# maindoline.net
KiCad netlist of a schematic drawn in Altium Designer
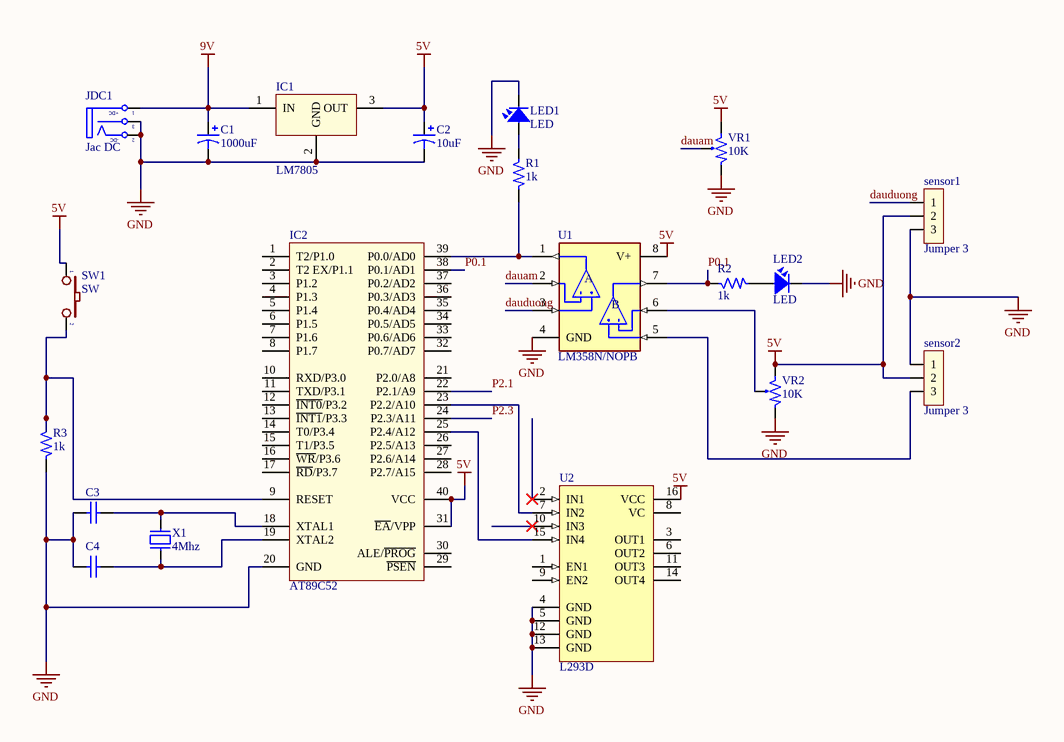
[diagram p0: maindoline.SchDoc]

(export (version "E")
  (design (tool "Eeschema 10.0.6"))
  (components
    (comp (ref "C1")
      (value "1000uF")
      (footprint "C5mm")
      (description "Polarized Capacitor (Axial)")
      (fields (field (name "PUBLISHER") "Altium Limited"))
      (libsource (lib "My Library") (part "Cap Pol 5mm"))
    )
    (comp (ref "C2")
      (value "10uF")
      (footprint "C5mm")
      (description "Polarized Capacitor (Axial)")
      (fields (field (name "PUBLISHER") "Altium Limited"))
      (libsource (lib "My Library") (part "Cap Pol 5mm"))
    )
    (comp (ref "C3")
      (value "22pF")
      (footprint "C0805")
      (description "Capacitor")
      (fields (field (name "PUBLISHER") "Altium Limited"))
      (libsource (lib "My Library") (part "CapSMD"))
    )
    (comp (ref "C4")
      (value "22pF")
      (footprint "C0805")
      (description "Capacitor")
      (fields (field (name "PUBLISHER") "Altium Limited"))
      (libsource (lib "My Library") (part "CapSMD"))
    )
    (comp (ref "IC1")
      (value "LM7805")
      (footprint "QTO-220")
      (description "On ap +, from + 5 to + 24VDC")
      (libsource (lib "My Library") (part "LM78xx"))
    )
    (comp (ref "IC2")
      (value "AT89C52")
      (footprint "DIP40/W0.6")
      (description "Atmel AT89C52, 8k Byte Flash Memory , 40 Pin")
      (libsource (lib "My Library") (part "AT89C52"))
    )
    (comp (ref "JDC1")
      (value "Jac DC")
      (footprint "DC-IN")
      (description "Jac DC input")
      (libsource (lib "My Library") (part "DCIN"))
    )
    (comp (ref "LED1")
      (value "LED")
      (footprint "LED-3")
      (description "LED Single colour Green and Red")
      (libsource (lib "My Library") (part "LED"))
    )
    (comp (ref "LED2")
      (value "LED")
      (footprint "LED-3")
      (description "LED Single colour Green and Red")
      (libsource (lib "My Library") (part "LED"))
    )
    (comp (ref "R1")
      (value "1k")
      (footprint "RES-SMD-0805")
      (description "Resistor 1/4W")
      (libsource (lib "My Library") (part "R"))
    )
    (comp (ref "R2")
      (value "1k")
      (footprint "RES-SMD-0805")
      (description "Resistor 1/4W")
      (libsource (lib "My Library") (part "R"))
    )
    (comp (ref "R3")
      (value "1k")
      (footprint "RES-SMD-0805")
      (description "Resistor 1/4W")
      (libsource (lib "My Library") (part "R"))
    )
    (comp (ref "sensor1") (value "Jumper 3") (footprint "JP3") (libsource (lib "My Library") (part "JP3")))
    (comp (ref "sensor2") (value "Jumper 3") (footprint "JP3") (libsource (lib "My Library") (part "JP3")))
    (comp (ref "SW1")
      (value "SW")
      (footprint "SW2")
      (description "Switch button 2 pin")
      (libsource (lib "My Library") (part "SW2"))
    )
    (comp (ref "U1")
      (value "LM358N/NOPB")
      (footprint "DIP794W45P254L959H508Q8")
      (libsource (lib "LM358N_NOPB") (part "LM358N/NOPB"))
    )
    (comp (ref "U2")
      (value "L293D")
      (footprint "DIP880W50P254L2000H510Q16")
      (description "Push-Pull Four Channel Driver With Diode")
      (fields (field (name "PUBLISHER") "Altium Limited"))
      (libsource (lib "My Library") (part "L293D"))
    )
    (comp (ref "VR1")
      (value "10K")
      (footprint "VR")
      (description "Var Resistor")
      (libsource (lib "My Library") (part "VR1"))
    )
    (comp (ref "VR2")
      (value "10K")
      (footprint "VR")
      (description "Var Resistor")
      (libsource (lib "My Library") (part "VR1"))
    )
    (comp (ref "X1")
      (value "4Mhz")
      (footprint "XT2")
      (description "Crystal For all Crystal 2pin.")
      (libsource (lib "My Library") (part "XT2"))
    )
  )
  (nets
    (net (code "1") (name "/P0.1") (class "Default")
      (node (ref "IC2") (pin "38") (pinfunction "P0.1/AD1_38") (pintype "passive"))
      (node (ref "R2") (pin "1") (pinfunction "1_1") (pintype "passive"))
      (node (ref "U1") (pin "7") (pinfunction "OUTB_7") (pintype "output"))
    )
    (net (code "2") (name "/P2.1") (class "Default")
      (node (ref "IC2") (pin "22") (pinfunction "P2.1/A9_22") (pintype "passive"))
    )
    (net (code "3") (name "/P2.3") (class "Default")
      (node (ref "IC2") (pin "24") (pinfunction "P2.3/A11_24") (pintype "passive"))
    )
    (net (code "4") (name "/dauam") (class "Default")
      (node (ref "U1") (pin "2") (pinfunction "-INA_2") (pintype "input"))
      (node (ref "VR1") (pin "2") (pinfunction "2_2") (pintype "passive"))
    )
    (net (code "5") (name "/dauduong") (class "Default")
      (node (ref "U1") (pin "3") (pinfunction "+INA_3") (pintype "input"))
      (node (ref "sensor1") (pin "1") (pinfunction "1_1") (pintype "passive"))
    )
    (net (code "6") (name "5V") (class "Default")
      (node (ref "C2") (pin "1") (pinfunction "1_1") (pintype "passive"))
      (node (ref "IC1") (pin "3") (pinfunction "OUT_3") (pintype "passive"))
      (node (ref "IC2") (pin "31") (pinfunction "~{EA}/VPP_31") (pintype "passive"))
      (node (ref "IC2") (pin "40") (pinfunction "VCC_40") (pintype "power_in"))
      (node (ref "SW1") (pin "1") (pinfunction "1_1") (pintype "passive"))
      (node (ref "U1") (pin "8") (pinfunction "V+_8") (pintype "power_in"))
      (node (ref "U2") (pin "16") (pinfunction "VCC_16") (pintype "power_in"))
      (node (ref "VR1") (pin "3") (pinfunction "3_3") (pintype "passive"))
      (node (ref "VR2") (pin "3") (pinfunction "3_3") (pintype "passive"))
      (node (ref "sensor1") (pin "2") (pinfunction "2_2") (pintype "passive"))
      (node (ref "sensor2") (pin "2") (pinfunction "2_2") (pintype "passive"))
    )
    (net (code "7") (name "9V") (class "Default")
      (node (ref "C1") (pin "1") (pinfunction "1_1") (pintype "passive"))
      (node (ref "IC1") (pin "1") (pinfunction "IN_1") (pintype "passive"))
      (node (ref "JDC1") (pin "1") (pinfunction "T_1") (pintype "passive"))
    )
    (net (code "8") (name "GND") (class "Default")
      (node (ref "C1") (pin "2") (pinfunction "2_2") (pintype "passive"))
      (node (ref "C2") (pin "2") (pinfunction "2_2") (pintype "passive"))
      (node (ref "C3") (pin "1") (pinfunction "1_1") (pintype "passive"))
      (node (ref "C4") (pin "1") (pinfunction "1_1") (pintype "passive"))
      (node (ref "IC1") (pin "2") (pinfunction "GND_2") (pintype "passive"))
      (node (ref "IC2") (pin "20") (pinfunction "GND_20") (pintype "open_emitter"))
      (node (ref "JDC1") (pin "2") (pinfunction "TN_2") (pintype "passive"))
      (node (ref "JDC1") (pin "3") (pinfunction "S_3") (pintype "power_in"))
      (node (ref "LED1") (pin "2") (pinfunction "2_2") (pintype "passive"))
      (node (ref "LED2") (pin "2") (pinfunction "2_2") (pintype "passive"))
      (node (ref "R3") (pin "2") (pinfunction "2_2") (pintype "passive"))
      (node (ref "U1") (pin "4") (pinfunction "GND_4") (pintype "power_in"))
      (node (ref "U2") (pin "12") (pinfunction "GND_12") (pintype "power_in"))
      (node (ref "U2") (pin "13") (pinfunction "GND_13") (pintype "power_in"))
      (node (ref "U2") (pin "4") (pinfunction "GND_4") (pintype "power_in"))
      (node (ref "U2") (pin "5") (pinfunction "GND_5") (pintype "power_in"))
      (node (ref "VR1") (pin "1") (pinfunction "1_1") (pintype "passive"))
      (node (ref "VR2") (pin "1") (pinfunction "1_1") (pintype "passive"))
      (node (ref "sensor1") (pin "3") (pinfunction "3_3") (pintype "passive"))
      (node (ref "sensor2") (pin "1") (pinfunction "1_1") (pintype "passive"))
    )
    (net (code "9") (name "Net-(IC2-P0.0{slash}AD0)") (class "Default")
      (node (ref "IC2") (pin "39") (pinfunction "P0.0/AD0_39") (pintype "passive"))
      (node (ref "R1") (pin "2") (pinfunction "2_2") (pintype "passive"))
      (node (ref "U1") (pin "1") (pinfunction "OUTA_1") (pintype "output"))
    )
    (net (code "10") (name "Net-(IC2-P2.2{slash}A10)") (class "Default")
      (node (ref "IC2") (pin "23") (pinfunction "P2.2/A10_23") (pintype "passive"))
      (node (ref "U2") (pin "7") (pinfunction "IN2_7") (pintype "input"))
    )
    (net (code "11") (name "Net-(IC2-P2.4{slash}A12)") (class "Default")
      (node (ref "IC2") (pin "25") (pinfunction "P2.4/A12_25") (pintype "passive"))
      (node (ref "U2") (pin "15") (pinfunction "IN4_15") (pintype "input"))
    )
    (net (code "12") (name "Net-(IC2-RESET)") (class "Default")
      (node (ref "IC2") (pin "9") (pinfunction "RESET_9") (pintype "passive"))
      (node (ref "R3") (pin "1") (pinfunction "1_1") (pintype "passive"))
      (node (ref "SW1") (pin "2") (pinfunction "2_2") (pintype "passive"))
    )
    (net (code "13") (name "Net-(IC2-XTAL1)") (class "Default")
      (node (ref "C3") (pin "2") (pinfunction "2_2") (pintype "passive"))
      (node (ref "IC2") (pin "18") (pinfunction "XTAL1_18") (pintype "passive"))
      (node (ref "X1") (pin "1") (pinfunction "1_1") (pintype "passive"))
    )
    (net (code "14") (name "Net-(IC2-XTAL2)") (class "Default")
      (node (ref "C4") (pin "2") (pinfunction "2_2") (pintype "passive"))
      (node (ref "IC2") (pin "19") (pinfunction "XTAL2_19") (pintype "passive"))
      (node (ref "X1") (pin "2") (pinfunction "2_2") (pintype "passive"))
    )
    (net (code "15") (name "Net-(LED1-Pad1)") (class "Default")
      (node (ref "LED1") (pin "1") (pinfunction "1_1") (pintype "passive"))
      (node (ref "R1") (pin "1") (pinfunction "1_1") (pintype "passive"))
    )
    (net (code "16") (name "Net-(LED2-Pad1)") (class "Default")
      (node (ref "LED2") (pin "1") (pinfunction "1_1") (pintype "passive"))
      (node (ref "R2") (pin "2") (pinfunction "2_2") (pintype "passive"))
    )
    (net (code "17") (name "Net-(U1-+INB)") (class "Default")
      (node (ref "U1") (pin "5") (pinfunction "+INB_5") (pintype "input"))
      (node (ref "sensor2") (pin "3") (pinfunction "3_3") (pintype "passive"))
    )
    (net (code "18") (name "Net-(U1--INB)") (class "Default")
      (node (ref "U1") (pin "6") (pinfunction "-INB_6") (pintype "input"))
      (node (ref "VR2") (pin "2") (pinfunction "2_2") (pintype "passive"))
    )
    (net (code "19") (name "unconnected-(IC2-ALE{slash}~{PROG}-Pad30)") (class "Default")
      (node (ref "IC2") (pin "30") (pinfunction "ALE/~{PROG}_30") (pintype "passive"))
    )
    (net (code "20") (name "unconnected-(IC2-P0.2{slash}AD2-Pad37)") (class "Default")
      (node (ref "IC2") (pin "37") (pinfunction "P0.2/AD2_37") (pintype "passive"))
    )
    (net (code "21") (name "unconnected-(IC2-P0.3{slash}AD3-Pad36)") (class "Default")
      (node (ref "IC2") (pin "36") (pinfunction "P0.3/AD3_36") (pintype "passive"))
    )
    (net (code "22") (name "unconnected-(IC2-P0.4{slash}AD4-Pad35)") (class "Default")
      (node (ref "IC2") (pin "35") (pinfunction "P0.4/AD4_35") (pintype "passive"))
    )
    (net (code "23") (name "unconnected-(IC2-P0.5{slash}AD5-Pad34)") (class "Default")
      (node (ref "IC2") (pin "34") (pinfunction "P0.5/AD5_34") (pintype "passive"))
    )
    (net (code "24") (name "unconnected-(IC2-P0.6{slash}AD6-Pad33)") (class "Default")
      (node (ref "IC2") (pin "33") (pinfunction "P0.6/AD6_33") (pintype "passive"))
    )
    (net (code "25") (name "unconnected-(IC2-P0.7{slash}AD7-Pad32)") (class "Default")
      (node (ref "IC2") (pin "32") (pinfunction "P0.7/AD7_32") (pintype "passive"))
    )
    (net (code "26") (name "unconnected-(IC2-P1.2-Pad3)") (class "Default")
      (node (ref "IC2") (pin "3") (pinfunction "P1.2_3") (pintype "passive"))
    )
    (net (code "27") (name "unconnected-(IC2-P1.3-Pad4)") (class "Default")
      (node (ref "IC2") (pin "4") (pinfunction "P1.3_4") (pintype "passive"))
    )
    (net (code "28") (name "unconnected-(IC2-P1.4-Pad5)") (class "Default")
      (node (ref "IC2") (pin "5") (pinfunction "P1.4_5") (pintype "passive"))
    )
    (net (code "29") (name "unconnected-(IC2-P1.5-Pad6)") (class "Default")
      (node (ref "IC2") (pin "6") (pinfunction "P1.5_6") (pintype "passive"))
    )
    (net (code "30") (name "unconnected-(IC2-P1.6-Pad7)") (class "Default")
      (node (ref "IC2") (pin "7") (pinfunction "P1.6_7") (pintype "passive"))
    )
    (net (code "31") (name "unconnected-(IC2-P1.7-Pad8)") (class "Default")
      (node (ref "IC2") (pin "8") (pinfunction "P1.7_8") (pintype "passive"))
    )
    (net (code "32") (name "unconnected-(IC2-P2.0{slash}A8-Pad21)") (class "Default")
      (node (ref "IC2") (pin "21") (pinfunction "P2.0/A8_21") (pintype "passive"))
    )
    (net (code "33") (name "unconnected-(IC2-P2.5{slash}A13-Pad26)") (class "Default")
      (node (ref "IC2") (pin "26") (pinfunction "P2.5/A13_26") (pintype "passive"))
    )
    (net (code "34") (name "unconnected-(IC2-P2.6{slash}A14-Pad27)") (class "Default")
      (node (ref "IC2") (pin "27") (pinfunction "P2.6/A14_27") (pintype "passive"))
    )
    (net (code "35") (name "unconnected-(IC2-P2.7{slash}A15-Pad28)") (class "Default")
      (node (ref "IC2") (pin "28") (pinfunction "P2.7/A15_28") (pintype "passive"))
    )
    (net (code "36") (name "unconnected-(IC2-RXD{slash}P3.0-Pad10)") (class "Default")
      (node (ref "IC2") (pin "10") (pinfunction "RXD/P3.0_10") (pintype "passive"))
    )
    (net (code "37") (name "unconnected-(IC2-T0{slash}P3.4-Pad14)") (class "Default")
      (node (ref "IC2") (pin "14") (pinfunction "T0/P3.4_14") (pintype "passive"))
    )
    (net (code "38") (name "unconnected-(IC2-T1{slash}P3.5-Pad15)") (class "Default")
      (node (ref "IC2") (pin "15") (pinfunction "T1/P3.5_15") (pintype "passive"))
    )
    (net (code "39") (name "unconnected-(IC2-T2_EX{slash}P1.1-Pad2)") (class "Default")
      (node (ref "IC2") (pin "2") (pinfunction "T2_EX/P1.1_2") (pintype "passive"))
    )
    (net (code "40") (name "unconnected-(IC2-T2{slash}P1.0-Pad1)") (class "Default")
      (node (ref "IC2") (pin "1") (pinfunction "T2/P1.0_1") (pintype "passive"))
    )
    (net (code "41") (name "unconnected-(IC2-TXD{slash}P3.1-Pad11)") (class "Default")
      (node (ref "IC2") (pin "11") (pinfunction "TXD/P3.1_11") (pintype "passive"))
    )
    (net (code "42") (name "unconnected-(IC2-~{INT0}{slash}P3.2-Pad12)") (class "Default")
      (node (ref "IC2") (pin "12") (pinfunction "~{INT0}/P3.2_12") (pintype "passive"))
    )
    (net (code "43") (name "unconnected-(IC2-~{INT1}{slash}P3.3-Pad13)") (class "Default")
      (node (ref "IC2") (pin "13") (pinfunction "~{INT1}/P3.3_13") (pintype "passive"))
    )
    (net (code "44") (name "unconnected-(IC2-~{PSEN}-Pad29)") (class "Default")
      (node (ref "IC2") (pin "29") (pinfunction "~{PSEN}_29") (pintype "passive"))
    )
    (net (code "45") (name "unconnected-(IC2-~{RD}{slash}P3.7-Pad17)") (class "Default")
      (node (ref "IC2") (pin "17") (pinfunction "~{RD}/P3.7_17") (pintype "passive"))
    )
    (net (code "46") (name "unconnected-(IC2-~{WR}{slash}P3.6-Pad16)") (class "Default")
      (node (ref "IC2") (pin "16") (pinfunction "~{WR}/P3.6_16") (pintype "passive"))
    )
    (net (code "47") (name "unconnected-(U2-EN1-Pad1)") (class "Default")
      (node (ref "U2") (pin "1") (pinfunction "EN1_1") (pintype "input"))
    )
    (net (code "48") (name "unconnected-(U2-EN2-Pad9)") (class "Default")
      (node (ref "U2") (pin "9") (pinfunction "EN2_9") (pintype "input"))
    )
    (net (code "49") (name "unconnected-(U2-IN1-Pad2)") (class "Default")
      (node (ref "U2") (pin "2") (pinfunction "IN1_2") (pintype "input+no_connect"))
    )
    (net (code "50") (name "unconnected-(U2-IN3-Pad10)") (class "Default")
      (node (ref "U2") (pin "10") (pinfunction "IN3_10") (pintype "input+no_connect"))
    )
    (net (code "51") (name "unconnected-(U2-OUT1-Pad3)") (class "Default")
      (node (ref "U2") (pin "3") (pinfunction "OUT1_3") (pintype "tri_state"))
    )
    (net (code "52") (name "unconnected-(U2-OUT2-Pad6)") (class "Default")
      (node (ref "U2") (pin "6") (pinfunction "OUT2_6") (pintype "tri_state"))
    )
    (net (code "53") (name "unconnected-(U2-OUT3-Pad11)") (class "Default")
      (node (ref "U2") (pin "11") (pinfunction "OUT3_11") (pintype "tri_state"))
    )
    (net (code "54") (name "unconnected-(U2-OUT4-Pad14)") (class "Default")
      (node (ref "U2") (pin "14") (pinfunction "OUT4_14") (pintype "tri_state"))
    )
    (net (code "55") (name "unconnected-(U2-VC-Pad8)") (class "Default")
      (node (ref "U2") (pin "8") (pinfunction "VC_8") (pintype "power_in"))
    )
  )
)
